# main_sch.net
KiCad netlist of a schematic drawn in Altium Designer
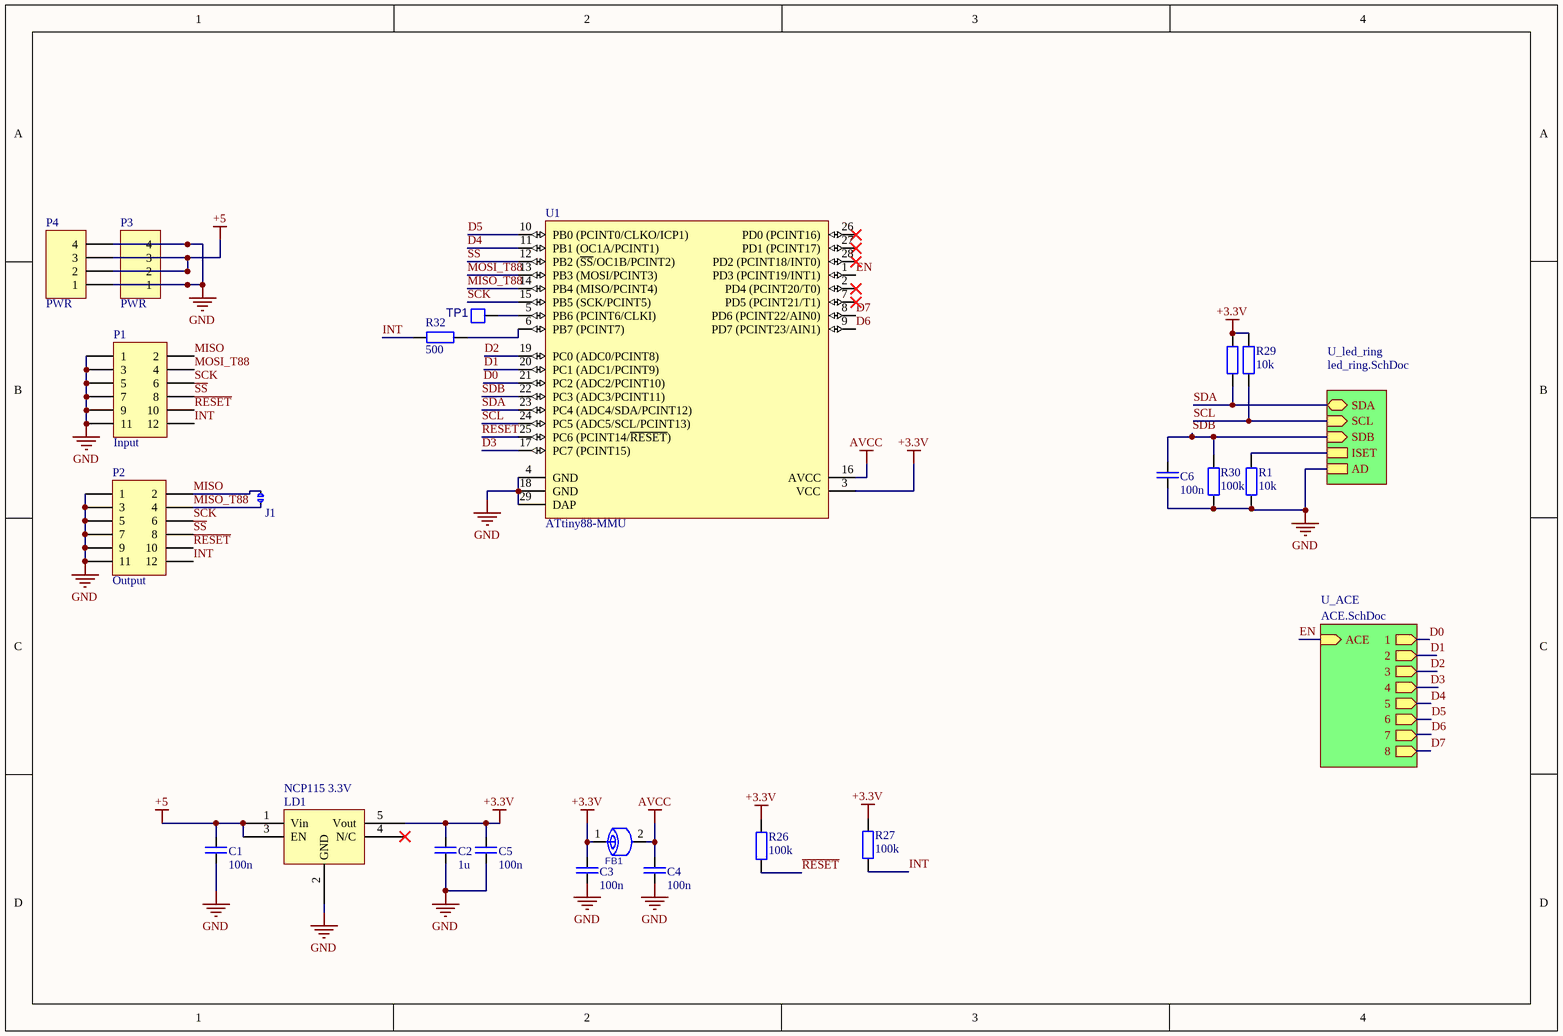
[diagram p0: main_sch.SchDoc]

(export (version "E")
  (design (tool "Eeschema 10.0.6"))
  (components
    (comp (ref "C1")
      (value "100n")
      (footprint "R1005_0402i_L")
      (description "Capacitor")
      (libsource (lib "General") (part "C"))
    )
    (comp (ref "C2")
      (value "1u")
      (footprint "C1608_0603I_L")
      (description "Capacitor")
      (libsource (lib "General") (part "C"))
    )
    (comp (ref "C3")
      (value "100n")
      (footprint "R1005_0402i_L")
      (description "Capacitor")
      (libsource (lib "General") (part "C"))
    )
    (comp (ref "C4")
      (value "100n")
      (footprint "R1005_0402i_L")
      (description "Capacitor")
      (libsource (lib "General") (part "C"))
    )
    (comp (ref "C5")
      (value "100n")
      (footprint "R1005_0402i_L")
      (description "Capacitor")
      (libsource (lib "General") (part "C"))
    )
    (comp (ref "C6")
      (value "100n")
      (footprint "R1005_0402i_L")
      (description "Capacitor")
      (libsource (lib "General") (part "C"))
    )
    (comp (ref "FB1")
      (value "FERITTE BEAD")
      (footprint "R1608_0603I_L")
      (libsource (lib "General") (part "FERITTE BEAD"))
    )
    (comp (ref "J1")
      (value "Terminator")
      (footprint "solderJumper")
      (libsource (lib "Kon_Tipk") (part "JMP_mini"))
    )
    (comp (ref "LD1")
      (value "NCP115 3.3V")
      (footprint "TSOP95P280X110-6L")
      (libsource (lib "led_ring") (part "NCP115 3.3V"))
    )
    (comp (ref "P1")
      (value "Input")
      (footprint "1.27mm SMD conn")
      (description "Header, 6-Pin, Dual row")
      (fields (field (name "PUBLISHER") "Altium Limited"))
      (libsource (lib "Miscellaneous Connectors") (part "Header 6X2"))
    )
    (comp (ref "P2")
      (value "Output")
      (footprint "1.27mm SMD conn")
      (description "Header, 6-Pin, Dual row")
      (fields (field (name "PUBLISHER") "Altium Limited"))
      (libsource (lib "Miscellaneous Connectors") (part "Header 6X2"))
    )
    (comp (ref "P3")
      (value "PWR")
      (footprint "HDR1X4")
      (description "Header, 4-Pin")
      (fields (field (name "PUBLISHER") "Altium Limited"))
      (libsource (lib "Miscellaneous Connectors") (part "Header 4"))
    )
    (comp (ref "P4")
      (value "PWR")
      (footprint "HDR1X4")
      (description "Header, 4-Pin")
      (fields (field (name "PUBLISHER") "Altium Limited"))
      (libsource (lib "Miscellaneous Connectors") (part "Header 4"))
    )
    (comp (ref "R1")
      (value "10k")
      (footprint "R1005_0402i_L")
      (description "R")
      (libsource (lib "General") (part "R"))
    )
    (comp (ref "R26")
      (value "100k")
      (footprint "R1005_0402i_L")
      (description "R")
      (libsource (lib "General") (part "R"))
    )
    (comp (ref "R27")
      (value "100k")
      (footprint "R1005_0402i_L")
      (description "R")
      (libsource (lib "General") (part "R"))
    )
    (comp (ref "R28")
      (value "10k")
      (footprint "R1005_0402i_L")
      (description "R")
      (libsource (lib "General") (part "R"))
    )
    (comp (ref "R29")
      (value "10k")
      (footprint "R1005_0402i_L")
      (description "R")
      (libsource (lib "General") (part "R"))
    )
    (comp (ref "R30")
      (value "100k")
      (footprint "R1005_0402i_L")
      (description "R")
      (libsource (lib "General") (part "R"))
    )
    (comp (ref "R32")
      (value "500")
      (footprint "R1005_0402i_L")
      (description "R")
      (libsource (lib "General") (part "R"))
    )
    (comp (ref "TP1") (value "PAD") (footprint "PAD") (libsource (lib "General") (part "PAD")))
    (comp (ref "U1")
      (value "ATtiny88-MMU")
      (footprint "28M1_N")
      (fields (field (name "PUBLISHER") "Altium Limited"))
      (libsource (lib "Atmel Microcontroller 8-Bit tinyAVR") (part "ATtiny88-MMU"))
    )
  )
  (nets
    (net (code "1") (name "+3.3V") (class "Default")
      (node (ref "C2") (pin "1") (pinfunction "1_1") (pintype "passive"))
      (node (ref "C3") (pin "1") (pinfunction "1_1") (pintype "passive"))
      (node (ref "C5") (pin "1") (pinfunction "1_1") (pintype "passive"))
      (node (ref "FB1") (pin "1") (pintype "passive"))
      (node (ref "LD1") (pin "5") (pinfunction "Vout_5") (pintype "passive"))
      (node (ref "R26") (pin "1") (pintype "passive"))
      (node (ref "R27") (pin "1") (pintype "passive"))
      (node (ref "R28") (pin "1") (pintype "passive"))
      (node (ref "R29") (pin "1") (pintype "passive"))
      (node (ref "U1") (pin "3") (pinfunction "VCC_3") (pintype "power_in"))
    )
    (net (code "2") (name "+5") (class "Default")
      (node (ref "C1") (pin "1") (pinfunction "1_1") (pintype "passive"))
      (node (ref "LD1") (pin "1") (pinfunction "Vin_1") (pintype "passive"))
      (node (ref "LD1") (pin "3") (pinfunction "EN_3") (pintype "passive"))
      (node (ref "P3") (pin "2") (pinfunction "2_2") (pintype "passive"))
      (node (ref "P3") (pin "3") (pinfunction "3_3") (pintype "passive"))
      (node (ref "P4") (pin "2") (pinfunction "2_2") (pintype "passive"))
      (node (ref "P4") (pin "3") (pinfunction "3_3") (pintype "passive"))
    )
    (net (code "3") (name "/D0") (class "Default")
      (node (ref "U1") (pin "21") (pinfunction "PC2_(ADC2/PCINT10)_21") (pintype "bidirectional"))
    )
    (net (code "4") (name "/D1") (class "Default")
      (node (ref "U1") (pin "20") (pinfunction "PC1_(ADC1/PCINT9)_20") (pintype "bidirectional"))
    )
    (net (code "5") (name "/D2") (class "Default")
      (node (ref "U1") (pin "19") (pinfunction "PC0_(ADC0/PCINT8)_19") (pintype "bidirectional"))
    )
    (net (code "6") (name "/D3") (class "Default")
      (node (ref "U1") (pin "17") (pinfunction "PC7_(PCINT15)_17") (pintype "bidirectional"))
    )
    (net (code "7") (name "/D4") (class "Default")
      (node (ref "U1") (pin "11") (pinfunction "PB1_(OC1A/PCINT1)_11") (pintype "bidirectional"))
    )
    (net (code "8") (name "/D5") (class "Default")
      (node (ref "U1") (pin "10") (pinfunction "PB0_(PCINT0/CLKO/ICP1)_10") (pintype "bidirectional"))
    )
    (net (code "9") (name "/D6") (class "Default")
      (node (ref "U1") (pin "9") (pinfunction "PD7_(PCINT23/AIN1)_9") (pintype "bidirectional"))
    )
    (net (code "10") (name "/D7") (class "Default")
      (node (ref "U1") (pin "8") (pinfunction "PD6_(PCINT22/AIN0)_8") (pintype "bidirectional"))
    )
    (net (code "11") (name "/EN") (class "Default")
      (node (ref "U1") (pin "1") (pinfunction "PD3_(PCINT19/INT1)_1") (pintype "bidirectional"))
    )
    (net (code "12") (name "/INT") (class "Default")
      (node (ref "P1") (pin "12") (pinfunction "12_12") (pintype "passive"))
      (node (ref "P2") (pin "12") (pinfunction "12_12") (pintype "passive"))
      (node (ref "R27") (pin "2") (pintype "passive"))
      (node (ref "R32") (pin "1") (pintype "passive"))
    )
    (net (code "13") (name "/ISET") (class "Default") (node (ref "R1") (pin "1") (pintype "passive")))
    (net (code "14") (name "/MISO") (class "Default")
      (node (ref "J1") (pin "2") (pinfunction "2_2") (pintype "passive"))
      (node (ref "P1") (pin "2") (pinfunction "2_2") (pintype "passive"))
      (node (ref "P2") (pin "2") (pinfunction "2_2") (pintype "passive"))
    )
    (net (code "15") (name "/MISO_T88") (class "Default")
      (node (ref "J1") (pin "1") (pinfunction "1_1") (pintype "passive"))
      (node (ref "P2") (pin "4") (pinfunction "4_4") (pintype "passive"))
      (node (ref "U1") (pin "14") (pinfunction "PB4_(MISO/PCINT4)_14") (pintype "bidirectional"))
    )
    (net (code "16") (name "/MOSI_T88") (class "Default")
      (node (ref "P1") (pin "4") (pinfunction "4_4") (pintype "passive"))
      (node (ref "U1") (pin "13") (pinfunction "PB3_(MOSI/PCINT3)_13") (pintype "bidirectional"))
    )
    (net (code "17") (name "/SCK") (class "Default")
      (node (ref "P1") (pin "6") (pinfunction "6_6") (pintype "passive"))
      (node (ref "P2") (pin "6") (pinfunction "6_6") (pintype "passive"))
      (node (ref "U1") (pin "15") (pinfunction "PB5_(SCK/PCINT5)_15") (pintype "bidirectional"))
    )
    (net (code "18") (name "/SCL") (class "Default")
      (node (ref "R29") (pin "2") (pintype "passive"))
      (node (ref "U1") (pin "24") (pinfunction "PC5_(ADC5/SCL/PCINT13)_24") (pintype "bidirectional"))
    )
    (net (code "19") (name "/SDA") (class "Default")
      (node (ref "R28") (pin "2") (pintype "passive"))
      (node (ref "U1") (pin "23") (pinfunction "PC4_(ADC4/SDA/PCINT12)_23") (pintype "bidirectional"))
    )
    (net (code "20") (name "/SDB") (class "Default")
      (node (ref "C6") (pin "1") (pinfunction "1_1") (pintype "passive"))
      (node (ref "R30") (pin "1") (pintype "passive"))
      (node (ref "U1") (pin "22") (pinfunction "PC3_(ADC3/PCINT11)_22") (pintype "bidirectional"))
    )
    (net (code "21") (name "/~{RESET}") (class "Default")
      (node (ref "P1") (pin "10") (pinfunction "10_10") (pintype "passive"))
      (node (ref "P2") (pin "10") (pinfunction "10_10") (pintype "passive"))
      (node (ref "R26") (pin "2") (pintype "passive"))
      (node (ref "U1") (pin "25") (pinfunction "PC6_(PCINT14/~{RESET})_25") (pintype "bidirectional"))
    )
    (net (code "22") (name "/~{SS}") (class "Default")
      (node (ref "P1") (pin "8") (pinfunction "8_8") (pintype "passive"))
      (node (ref "P2") (pin "8") (pinfunction "8_8") (pintype "passive"))
      (node (ref "U1") (pin "12") (pinfunction "PB2_(~{SS}/OC1B/PCINT2)_12") (pintype "bidirectional"))
    )
    (net (code "23") (name "AVCC") (class "Default")
      (node (ref "C4") (pin "1") (pinfunction "1_1") (pintype "passive"))
      (node (ref "FB1") (pin "2") (pintype "passive"))
      (node (ref "U1") (pin "16") (pinfunction "AVCC_16") (pintype "power_in"))
    )
    (net (code "24") (name "GND") (class "Default")
      (node (ref "C1") (pin "2") (pinfunction "2_2") (pintype "passive"))
      (node (ref "C2") (pin "2") (pinfunction "2_2") (pintype "passive"))
      (node (ref "C3") (pin "2") (pinfunction "2_2") (pintype "passive"))
      (node (ref "C4") (pin "2") (pinfunction "2_2") (pintype "passive"))
      (node (ref "C5") (pin "2") (pinfunction "2_2") (pintype "passive"))
      (node (ref "C6") (pin "2") (pinfunction "2_2") (pintype "passive"))
      (node (ref "LD1") (pin "2") (pinfunction "GND_2") (pintype "passive"))
      (node (ref "P1") (pin "1") (pinfunction "1_1") (pintype "passive"))
      (node (ref "P1") (pin "11") (pinfunction "11_11") (pintype "passive"))
      (node (ref "P1") (pin "3") (pinfunction "3_3") (pintype "passive"))
      (node (ref "P1") (pin "5") (pinfunction "5_5") (pintype "passive"))
      (node (ref "P1") (pin "7") (pinfunction "7_7") (pintype "passive"))
      (node (ref "P1") (pin "9") (pinfunction "9_9") (pintype "passive"))
      (node (ref "P2") (pin "1") (pinfunction "1_1") (pintype "passive"))
      (node (ref "P2") (pin "11") (pinfunction "11_11") (pintype "passive"))
      (node (ref "P2") (pin "3") (pinfunction "3_3") (pintype "passive"))
      (node (ref "P2") (pin "5") (pinfunction "5_5") (pintype "passive"))
      (node (ref "P2") (pin "7") (pinfunction "7_7") (pintype "passive"))
      (node (ref "P2") (pin "9") (pinfunction "9_9") (pintype "passive"))
      (node (ref "P3") (pin "1") (pinfunction "1_1") (pintype "passive"))
      (node (ref "P3") (pin "4") (pinfunction "4_4") (pintype "passive"))
      (node (ref "P4") (pin "1") (pinfunction "1_1") (pintype "passive"))
      (node (ref "P4") (pin "4") (pinfunction "4_4") (pintype "passive"))
      (node (ref "R1") (pin "2") (pintype "passive"))
      (node (ref "R30") (pin "2") (pintype "passive"))
      (node (ref "U1") (pin "18") (pinfunction "GND_18") (pintype "power_in"))
      (node (ref "U1") (pin "29") (pinfunction "DAP_29") (pintype "passive"))
      (node (ref "U1") (pin "4") (pinfunction "GND_4") (pintype "power_in"))
    )
    (net (code "25") (name "Net-(U1-PB6_(PCINT6{slash}CLKI))") (class "Default")
      (node (ref "TP1") (pin "1") (pinfunction "1_1") (pintype "passive"))
      (node (ref "U1") (pin "5") (pinfunction "PB6_(PCINT6/CLKI)_5") (pintype "bidirectional"))
    )
    (net (code "26") (name "Net-(U1-PB7_(PCINT7))") (class "Default")
      (node (ref "R32") (pin "2") (pintype "passive"))
      (node (ref "U1") (pin "6") (pinfunction "PB7_(PCINT7)_6") (pintype "bidirectional"))
    )
    (net (code "27") (name "unconnected-(LD1-N{slash}C-Pad4)") (class "Default")
      (node (ref "LD1") (pin "4") (pinfunction "N/C_4") (pintype "passive+no_connect"))
    )
    (net (code "28") (name "unconnected-(U1-PD0_(PCINT16)-Pad26)") (class "Default")
      (node (ref "U1") (pin "26") (pinfunction "PD0_(PCINT16)_26") (pintype "bidirectional+no_connect"))
    )
    (net (code "29") (name "unconnected-(U1-PD1_(PCINT17)-Pad27)") (class "Default")
      (node (ref "U1") (pin "27") (pinfunction "PD1_(PCINT17)_27") (pintype "bidirectional+no_connect"))
    )
    (net (code "30") (name "unconnected-(U1-PD2_(PCINT18{slash}INT0)-Pad28)") (class "Default")
      (node (ref "U1") (pin "28") (pinfunction "PD2_(PCINT18/INT0)_28") (pintype "bidirectional+no_connect"))
    )
    (net (code "31") (name "unconnected-(U1-PD4_(PCINT20{slash}T0)-Pad2)") (class "Default")
      (node (ref "U1") (pin "2") (pinfunction "PD4_(PCINT20/T0)_2") (pintype "bidirectional+no_connect"))
    )
    (net (code "32") (name "unconnected-(U1-PD5_(PCINT21{slash}T1)-Pad7)") (class "Default")
      (node (ref "U1") (pin "7") (pinfunction "PD5_(PCINT21/T1)_7") (pintype "bidirectional+no_connect"))
    )
  )
)
